# development_board.net
KiCad netlist of a schematic drawn in EAGLE
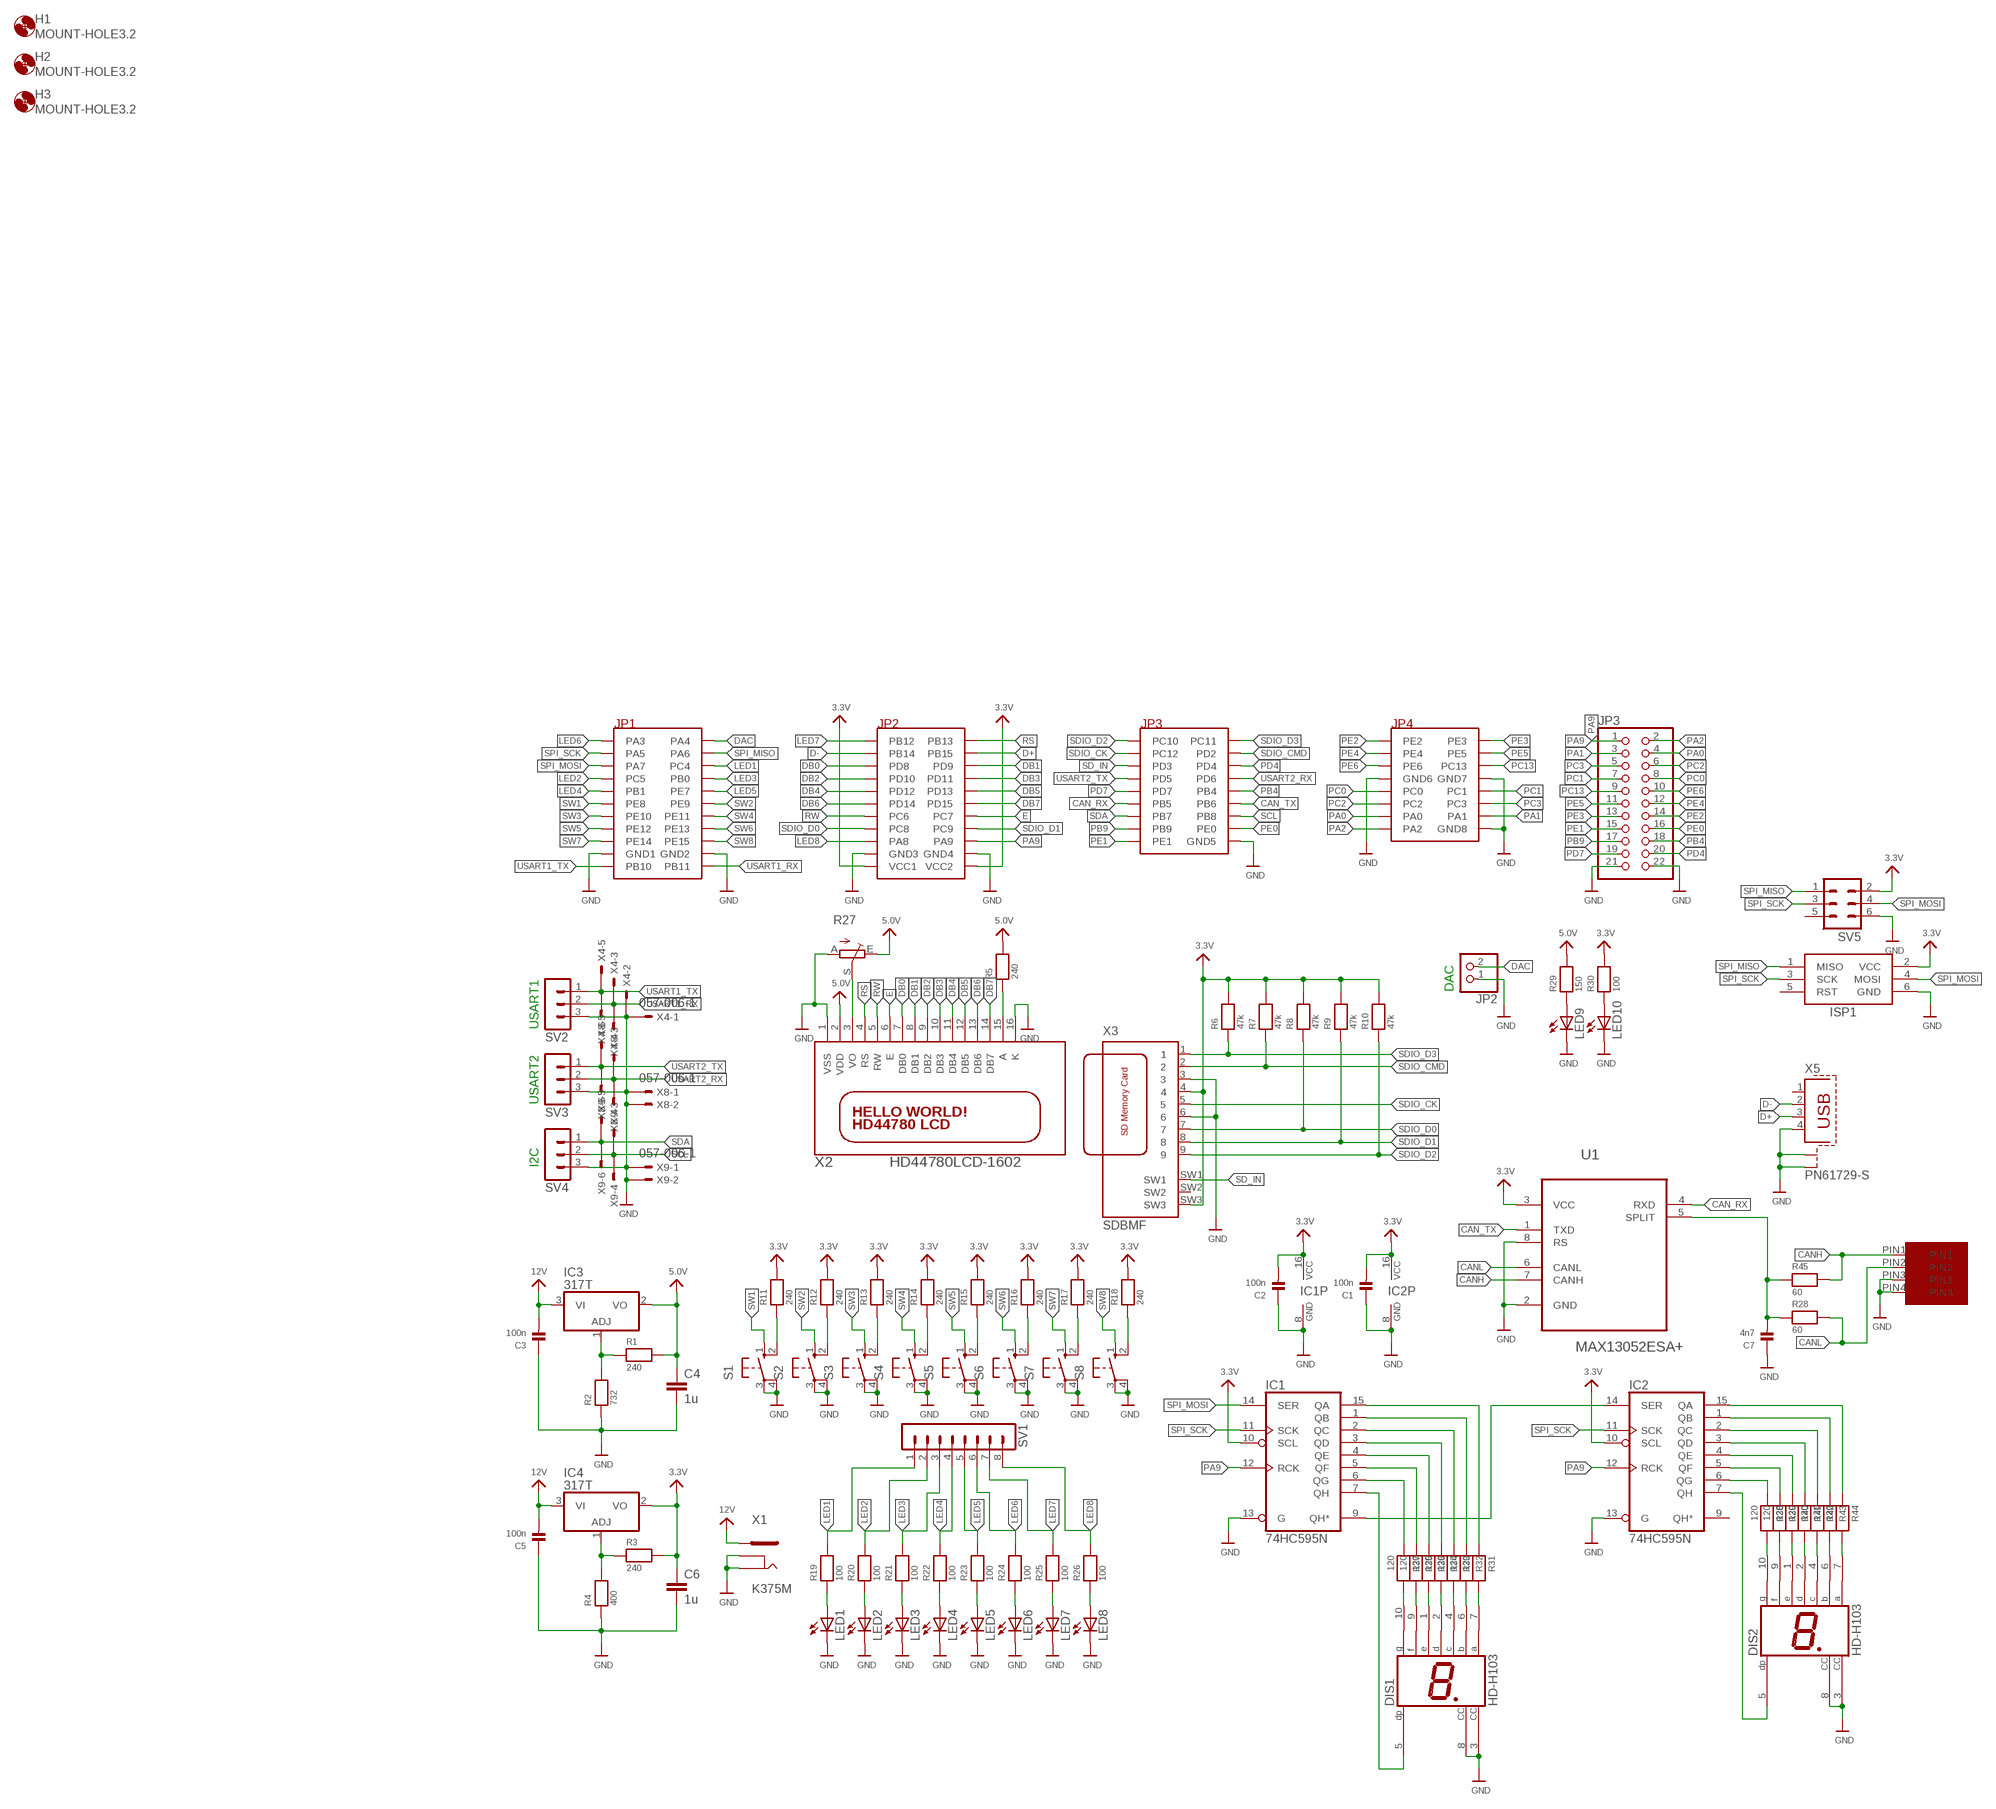
[diagram p0: schematic, sheet 1]

(export (version "E")
  (design (tool "Eeschema 10.0.6"))
  (components
    (comp (ref "C1")
      (value "100n")
      (footprint "eagle-import:_0603")
      (libsource (lib "eagle-import") (part "CAP_CERAMIC_0603"))
    )
    (comp (ref "C2")
      (value "100n")
      (footprint "eagle-import:_0603")
      (libsource (lib "eagle-import") (part "CAP_CERAMIC_0603"))
    )
    (comp (ref "C3")
      (value "100n")
      (footprint "eagle-import:_0603")
      (libsource (lib "eagle-import") (part "CAP_CERAMIC_0603"))
    )
    (comp (ref "C4")
      (value "1u")
      (footprint "eagle-import:C050-035X075")
      (libsource (lib "eagle-import") (part "C-EU050-035X075"))
    )
    (comp (ref "C5")
      (value "100n")
      (footprint "eagle-import:_0603")
      (libsource (lib "eagle-import") (part "CAP_CERAMIC_0603"))
    )
    (comp (ref "C6")
      (value "1u")
      (footprint "eagle-import:C050-035X075")
      (libsource (lib "eagle-import") (part "C-EU050-035X075"))
    )
    (comp (ref "C7")
      (value "4n7")
      (footprint "eagle-import:_0603")
      (libsource (lib "eagle-import") (part "CAP_CERAMIC_0603"))
    )
    (comp (ref "DIS1")
      (value "HD-H103")
      (footprint "eagle-import:HDSP-M")
      (libsource (lib "eagle-import") (part "HD-H103"))
    )
    (comp (ref "DIS2")
      (value "HD-H103")
      (footprint "eagle-import:HDSP-M")
      (libsource (lib "eagle-import") (part "HD-H103"))
    )
    (comp (ref "H1")
      (value "MOUNT-HOLE3.2")
      (footprint "eagle-import:3,2")
      (libsource (lib "eagle-import") (part "MOUNT-HOLE3.2"))
    )
    (comp (ref "H2")
      (value "MOUNT-HOLE3.2")
      (footprint "eagle-import:3,2")
      (libsource (lib "eagle-import") (part "MOUNT-HOLE3.2"))
    )
    (comp (ref "H3")
      (value "MOUNT-HOLE3.2")
      (footprint "eagle-import:3,2")
      (libsource (lib "eagle-import") (part "MOUNT-HOLE3.2"))
    )
    (comp (ref "IC1")
      (value "74HC595N")
      (footprint "eagle-import:DIL16")
      (libsource (lib "eagle-import") (part "74595NHC"))
    )
    (comp (ref "IC2")
      (value "74HC595N")
      (footprint "eagle-import:DIL16")
      (libsource (lib "eagle-import") (part "74595NHC"))
    )
    (comp (ref "IC3")
      (value "317T")
      (footprint "eagle-import:TO220H")
      (libsource (lib "eagle-import") (part "317T"))
    )
    (comp (ref "IC4")
      (value "317T")
      (footprint "eagle-import:TO220H")
      (libsource (lib "eagle-import") (part "317T"))
    )
    (comp (ref "ISP1")
      (value "AVRISP-BOX")
      (footprint "eagle-import:AVRISP-BOX")
      (libsource (lib "eagle-import") (part "AVRISP-BOX"))
    )
    (comp (ref "JP2")
      (value "HEADER-1X2ROUND")
      (footprint "eagle-import:1X02_ROUND")
      (libsource (lib "eagle-import") (part "HEADER-1X2ROUND"))
    )
    (comp (ref "JP3")
      (value "PINHD-2X11")
      (footprint "eagle-import:2X11")
      (libsource (lib "eagle-import") (part "PINHD-2X11"))
    )
    (comp (ref "LED1")
      (value "LED5MM")
      (footprint "eagle-import:LED5MM")
      (libsource (lib "eagle-import") (part "LED5MM"))
    )
    (comp (ref "LED2")
      (value "LED5MM")
      (footprint "eagle-import:LED5MM")
      (libsource (lib "eagle-import") (part "LED5MM"))
    )
    (comp (ref "LED3")
      (value "LED5MM")
      (footprint "eagle-import:LED5MM")
      (libsource (lib "eagle-import") (part "LED5MM"))
    )
    (comp (ref "LED4")
      (value "LED5MM")
      (footprint "eagle-import:LED5MM")
      (libsource (lib "eagle-import") (part "LED5MM"))
    )
    (comp (ref "LED5")
      (value "LED5MM")
      (footprint "eagle-import:LED5MM")
      (libsource (lib "eagle-import") (part "LED5MM"))
    )
    (comp (ref "LED6")
      (value "LED5MM")
      (footprint "eagle-import:LED5MM")
      (libsource (lib "eagle-import") (part "LED5MM"))
    )
    (comp (ref "LED7")
      (value "LED5MM")
      (footprint "eagle-import:LED5MM")
      (libsource (lib "eagle-import") (part "LED5MM"))
    )
    (comp (ref "LED8")
      (value "LED5MM")
      (footprint "eagle-import:LED5MM")
      (libsource (lib "eagle-import") (part "LED5MM"))
    )
    (comp (ref "LED9")
      (value "LED3MM")
      (footprint "eagle-import:LED3MM")
      (libsource (lib "eagle-import") (part "led_LED3MM"))
    )
    (comp (ref "LED10")
      (value "LED3MM")
      (footprint "eagle-import:LED3MM")
      (libsource (lib "eagle-import") (part "led_LED3MM"))
    )
    (comp (ref "R1")
      (value "240")
      (footprint "eagle-import:_0603")
      (libsource (lib "eagle-import") (part "RESISTOR_0603"))
    )
    (comp (ref "R2")
      (value "732")
      (footprint "eagle-import:_0603")
      (libsource (lib "eagle-import") (part "RESISTOR_0603"))
    )
    (comp (ref "R3")
      (value "240")
      (footprint "eagle-import:_0603")
      (libsource (lib "eagle-import") (part "RESISTOR_0603"))
    )
    (comp (ref "R4")
      (value "400")
      (footprint "eagle-import:_0603")
      (libsource (lib "eagle-import") (part "RESISTOR_0603"))
    )
    (comp (ref "R5")
      (value "240")
      (footprint "eagle-import:_0603")
      (libsource (lib "eagle-import") (part "RESISTOR_0603"))
    )
    (comp (ref "R6")
      (value "47k")
      (footprint "eagle-import:_0603")
      (libsource (lib "eagle-import") (part "RESISTOR_0603"))
    )
    (comp (ref "R7")
      (value "47k")
      (footprint "eagle-import:_0603")
      (libsource (lib "eagle-import") (part "RESISTOR_0603"))
    )
    (comp (ref "R8")
      (value "47k")
      (footprint "eagle-import:_0603")
      (libsource (lib "eagle-import") (part "RESISTOR_0603"))
    )
    (comp (ref "R9")
      (value "47k")
      (footprint "eagle-import:_0603")
      (libsource (lib "eagle-import") (part "RESISTOR_0603"))
    )
    (comp (ref "R10")
      (value "47k")
      (footprint "eagle-import:_0603")
      (libsource (lib "eagle-import") (part "RESISTOR_0603"))
    )
    (comp (ref "R11")
      (value "240")
      (footprint "eagle-import:_0603")
      (libsource (lib "eagle-import") (part "RESISTOR_0603"))
    )
    (comp (ref "R12")
      (value "240")
      (footprint "eagle-import:_0603")
      (libsource (lib "eagle-import") (part "RESISTOR_0603"))
    )
    (comp (ref "R13")
      (value "240")
      (footprint "eagle-import:_0603")
      (libsource (lib "eagle-import") (part "RESISTOR_0603"))
    )
    (comp (ref "R14")
      (value "240")
      (footprint "eagle-import:_0603")
      (libsource (lib "eagle-import") (part "RESISTOR_0603"))
    )
    (comp (ref "R15")
      (value "240")
      (footprint "eagle-import:_0603")
      (libsource (lib "eagle-import") (part "RESISTOR_0603"))
    )
    (comp (ref "R16")
      (value "240")
      (footprint "eagle-import:_0603")
      (libsource (lib "eagle-import") (part "RESISTOR_0603"))
    )
    (comp (ref "R17")
      (value "240")
      (footprint "eagle-import:_0603")
      (libsource (lib "eagle-import") (part "RESISTOR_0603"))
    )
    (comp (ref "R18")
      (value "240")
      (footprint "eagle-import:_0603")
      (libsource (lib "eagle-import") (part "RESISTOR_0603"))
    )
    (comp (ref "R19")
      (value "100")
      (footprint "eagle-import:_0603")
      (libsource (lib "eagle-import") (part "RESISTOR_0603"))
    )
    (comp (ref "R20")
      (value "100")
      (footprint "eagle-import:_0603")
      (libsource (lib "eagle-import") (part "RESISTOR_0603"))
    )
    (comp (ref "R21")
      (value "100")
      (footprint "eagle-import:_0603")
      (libsource (lib "eagle-import") (part "RESISTOR_0603"))
    )
    (comp (ref "R22")
      (value "100")
      (footprint "eagle-import:_0603")
      (libsource (lib "eagle-import") (part "RESISTOR_0603"))
    )
    (comp (ref "R23")
      (value "100")
      (footprint "eagle-import:_0603")
      (libsource (lib "eagle-import") (part "RESISTOR_0603"))
    )
    (comp (ref "R24")
      (value "100")
      (footprint "eagle-import:_0603")
      (libsource (lib "eagle-import") (part "RESISTOR_0603"))
    )
    (comp (ref "R25")
      (value "100")
      (footprint "eagle-import:_0603")
      (libsource (lib "eagle-import") (part "RESISTOR_0603"))
    )
    (comp (ref "R26")
      (value "100")
      (footprint "eagle-import:_0603")
      (libsource (lib "eagle-import") (part "RESISTOR_0603"))
    )
    (comp (ref "R27")
      (value "TRIM_EU-RJ9W")
      (footprint "eagle-import:RJ9W")
      (libsource (lib "eagle-import") (part "TRIM_EU-RJ9W"))
    )
    (comp (ref "R28")
      (value "60")
      (footprint "eagle-import:_0603")
      (libsource (lib "eagle-import") (part "RESISTOR_0603"))
    )
    (comp (ref "R29")
      (value "150")
      (footprint "eagle-import:_0603")
      (libsource (lib "eagle-import") (part "RESISTOR_0603"))
    )
    (comp (ref "R30")
      (value "100")
      (footprint "eagle-import:_0603")
      (libsource (lib "eagle-import") (part "RESISTOR_0603"))
    )
    (comp (ref "R31")
      (value "120")
      (footprint "eagle-import:_0603")
      (libsource (lib "eagle-import") (part "RESISTOR_0603"))
    )
    (comp (ref "R32")
      (value "120")
      (footprint "eagle-import:_0603")
      (libsource (lib "eagle-import") (part "RESISTOR_0603"))
    )
    (comp (ref "R33")
      (value "120")
      (footprint "eagle-import:_0603")
      (libsource (lib "eagle-import") (part "RESISTOR_0603"))
    )
    (comp (ref "R34")
      (value "120")
      (footprint "eagle-import:_0603")
      (libsource (lib "eagle-import") (part "RESISTOR_0603"))
    )
    (comp (ref "R35")
      (value "120")
      (footprint "eagle-import:_0603")
      (libsource (lib "eagle-import") (part "RESISTOR_0603"))
    )
    (comp (ref "R36")
      (value "120")
      (footprint "eagle-import:_0603")
      (libsource (lib "eagle-import") (part "RESISTOR_0603"))
    )
    (comp (ref "R37")
      (value "120")
      (footprint "eagle-import:_0603")
      (libsource (lib "eagle-import") (part "RESISTOR_0603"))
    )
    (comp (ref "R38")
      (value "120")
      (footprint "eagle-import:_0603")
      (libsource (lib "eagle-import") (part "RESISTOR_0603"))
    )
    (comp (ref "R39")
      (value "120")
      (footprint "eagle-import:_0603")
      (libsource (lib "eagle-import") (part "RESISTOR_0603"))
    )
    (comp (ref "R40")
      (value "120")
      (footprint "eagle-import:_0603")
      (libsource (lib "eagle-import") (part "RESISTOR_0603"))
    )
    (comp (ref "R41")
      (value "120")
      (footprint "eagle-import:_0603")
      (libsource (lib "eagle-import") (part "RESISTOR_0603"))
    )
    (comp (ref "R42")
      (value "120")
      (footprint "eagle-import:_0603")
      (libsource (lib "eagle-import") (part "RESISTOR_0603"))
    )
    (comp (ref "R43")
      (value "120")
      (footprint "eagle-import:_0603")
      (libsource (lib "eagle-import") (part "RESISTOR_0603"))
    )
    (comp (ref "R44")
      (value "120")
      (footprint "eagle-import:_0603")
      (libsource (lib "eagle-import") (part "RESISTOR_0603"))
    )
    (comp (ref "R45")
      (value "60")
      (footprint "eagle-import:_0603")
      (libsource (lib "eagle-import") (part "RESISTOR_0603"))
    )
    (comp (ref "S1")
      (value "10-XX")
      (footprint "eagle-import:B3F-10XX")
      (fields (field (name "MPN") "B3F-1000"))
      (libsource (lib "eagle-import") (part "10-XX"))
    )
    (comp (ref "S2")
      (value "10-XX")
      (footprint "eagle-import:B3F-10XX")
      (fields (field (name "MPN") "B3F-1000"))
      (libsource (lib "eagle-import") (part "10-XX"))
    )
    (comp (ref "S3")
      (value "10-XX")
      (footprint "eagle-import:B3F-10XX")
      (fields (field (name "MPN") "B3F-1000"))
      (libsource (lib "eagle-import") (part "10-XX"))
    )
    (comp (ref "S4")
      (value "10-XX")
      (footprint "eagle-import:B3F-10XX")
      (fields (field (name "MPN") "B3F-1000"))
      (libsource (lib "eagle-import") (part "10-XX"))
    )
    (comp (ref "S5")
      (value "10-XX")
      (footprint "eagle-import:B3F-10XX")
      (fields (field (name "MPN") "B3F-1000"))
      (libsource (lib "eagle-import") (part "10-XX"))
    )
    (comp (ref "S6")
      (value "10-XX")
      (footprint "eagle-import:B3F-10XX")
      (fields (field (name "MPN") "B3F-1000"))
      (libsource (lib "eagle-import") (part "10-XX"))
    )
    (comp (ref "S7")
      (value "10-XX")
      (footprint "eagle-import:B3F-10XX")
      (fields (field (name "MPN") "B3F-1000"))
      (libsource (lib "eagle-import") (part "10-XX"))
    )
    (comp (ref "S8")
      (value "10-XX")
      (footprint "eagle-import:B3F-10XX")
      (fields (field (name "MPN") "B3F-1000"))
      (libsource (lib "eagle-import") (part "10-XX"))
    )
    (comp (ref "SV1")
      (value "MA08-1")
      (footprint "eagle-import:MA08-1")
      (libsource (lib "eagle-import") (part "MA08-1"))
    )
    (comp (ref "SV2")
      (value "MA03-1")
      (footprint "eagle-import:MA03-1")
      (libsource (lib "eagle-import") (part "MA03-1"))
    )
    (comp (ref "SV3")
      (value "MA03-1")
      (footprint "eagle-import:MA03-1")
      (libsource (lib "eagle-import") (part "MA03-1"))
    )
    (comp (ref "SV4")
      (value "MA03-1")
      (footprint "eagle-import:MA03-1")
      (libsource (lib "eagle-import") (part "MA03-1"))
    )
    (comp (ref "SV5")
      (value "MA03-2")
      (footprint "eagle-import:MA03-2")
      (libsource (lib "eagle-import") (part "MA03-2"))
    )
    (comp (ref "U$1")
      (value "CPU-BOARD")
      (footprint "eagle-import:CPU-BOARD-JP1")
      (libsource (lib "eagle-import") (part "CPU-BOARD"))
    )
    (comp (ref "U$57")
      (value "MICROFIT4")
      (footprint "eagle-import:MICROFIT4SOCK")
      (libsource (lib "eagle-import") (part "MICROFIT4"))
    )
    (comp (ref "U1")
      (value "MAX13052ESA+")
      (footprint "eagle-import:SOIC127P600X175-8N")
      (libsource (lib "eagle-import") (part "MAX13052ESA+"))
    )
    (comp (ref "X1")
      (value "K375M")
      (footprint "eagle-import:K375M")
      (libsource (lib "eagle-import") (part "K375M"))
    )
    (comp (ref "X2")
      (value "HD44780LCD-1602")
      (footprint "eagle-import:LCD1602")
      (libsource (lib "eagle-import") (part "HD44780LCD-1602"))
    )
    (comp (ref "X3")
      (value "SDBMF")
      (footprint "eagle-import:SDBMF-009XXBXX2")
      (libsource (lib "eagle-import") (part "SDBMF"))
    )
    (comp (ref "X4")
      (value "057-006-1")
      (footprint "eagle-import:057-006-1")
      (fields (field (name "OC_FARNELL") "unknown") (field (name "OC_NEWARK") "unknown"))
      (libsource (lib "eagle-import") (part "057-006-1"))
    )
    (comp (ref "X5")
      (value "PN61729-S")
      (footprint "eagle-import:PN61729-S")
      (libsource (lib "eagle-import") (part "PN61729-S"))
    )
    (comp (ref "X8")
      (value "057-006-1")
      (footprint "eagle-import:057-006-1")
      (fields (field (name "OC_FARNELL") "unknown") (field (name "OC_NEWARK") "unknown"))
      (libsource (lib "eagle-import") (part "057-006-1"))
    )
    (comp (ref "X9")
      (value "057-006-1")
      (footprint "eagle-import:057-006-1")
      (fields (field (name "OC_FARNELL") "unknown") (field (name "OC_NEWARK") "unknown"))
      (libsource (lib "eagle-import") (part "057-006-1"))
    )
  )
  (nets
    (net (code "1") (name "3.3V") (class "Default")
      (node (ref "C1") (pin "2") (pinfunction "P$2_2") (pintype "passive"))
      (node (ref "C2") (pin "2") (pinfunction "P$2_2") (pintype "passive"))
      (node (ref "C6") (pin "1") (pinfunction "1_1") (pintype "passive"))
      (node (ref "IC1") (pin "10") (pinfunction "SCL_10") (pintype "input"))
      (node (ref "IC1") (pin "16") (pinfunction "VCC_16") (pintype "power_in"))
      (node (ref "IC2") (pin "10") (pinfunction "SCL_10") (pintype "input"))
      (node (ref "IC2") (pin "16") (pinfunction "VCC_16") (pintype "power_in"))
      (node (ref "IC4") (pin "2") (pinfunction "VO_2") (pintype "passive"))
      (node (ref "ISP1") (pin "2") (pinfunction "VCC_2") (pintype "power_in"))
      (node (ref "R10") (pin "2") (pinfunction "2_2") (pintype "passive"))
      (node (ref "R11") (pin "2") (pinfunction "2_2") (pintype "passive"))
      (node (ref "R12") (pin "2") (pinfunction "2_2") (pintype "passive"))
      (node (ref "R13") (pin "2") (pinfunction "2_2") (pintype "passive"))
      (node (ref "R14") (pin "2") (pinfunction "2_2") (pintype "passive"))
      (node (ref "R15") (pin "2") (pinfunction "2_2") (pintype "passive"))
      (node (ref "R16") (pin "2") (pinfunction "2_2") (pintype "passive"))
      (node (ref "R17") (pin "2") (pinfunction "2_2") (pintype "passive"))
      (node (ref "R18") (pin "2") (pinfunction "2_2") (pintype "passive"))
      (node (ref "R3") (pin "2") (pinfunction "2_2") (pintype "passive"))
      (node (ref "R30") (pin "2") (pinfunction "2_2") (pintype "passive"))
      (node (ref "R6") (pin "2") (pinfunction "2_2") (pintype "passive"))
      (node (ref "R7") (pin "2") (pinfunction "2_2") (pintype "passive"))
      (node (ref "R8") (pin "2") (pinfunction "2_2") (pintype "passive"))
      (node (ref "R9") (pin "2") (pinfunction "2_2") (pintype "passive"))
      (node (ref "SV5") (pin "2") (pinfunction "2_2") (pintype "passive"))
      (node (ref "U$1") (pin "P$43") (pinfunction "VCC1_P$43") (pintype "bidirectional"))
      (node (ref "U$1") (pin "P$44") (pinfunction "VCC2_P$44") (pintype "bidirectional"))
      (node (ref "U1") (pin "3") (pinfunction "VCC_3") (pintype "power_in"))
      (node (ref "X3") (pin "4") (pinfunction "4_4") (pintype "passive"))
      (node (ref "X3") (pin "SW3") (pinfunction "SW3_SW3") (pintype "passive"))
    )
    (net (code "2") (name "5.0V") (class "Default")
      (node (ref "C4") (pin "1") (pinfunction "1_1") (pintype "passive"))
      (node (ref "IC3") (pin "2") (pinfunction "VO_2") (pintype "passive"))
      (node (ref "R1") (pin "2") (pinfunction "2_2") (pintype "passive"))
      (node (ref "R27") (pin "E") (pinfunction "E_E") (pintype "passive"))
      (node (ref "R29") (pin "2") (pinfunction "2_2") (pintype "passive"))
      (node (ref "R5") (pin "2") (pinfunction "2_2") (pintype "passive"))
      (node (ref "X2") (pin "2") (pinfunction "VDD_2") (pintype "power_in"))
    )
    (net (code "3") (name "12V") (class "Default")
      (node (ref "C3") (pin "2") (pinfunction "P$2_2") (pintype "passive"))
      (node (ref "C5") (pin "2") (pinfunction "P$2_2") (pintype "passive"))
      (node (ref "IC3") (pin "3") (pinfunction "VI_3") (pintype "input"))
      (node (ref "IC4") (pin "3") (pinfunction "VI_3") (pintype "input"))
      (node (ref "X1") (pin "1") (pinfunction "1_1") (pintype "passive"))
    )
    (net (code "4") (name "CANH") (class "Default")
      (node (ref "R45") (pin "2") (pinfunction "2_2") (pintype "passive"))
      (node (ref "U$57") (pin "PIN1") (pinfunction "PIN1_PIN1") (pintype "bidirectional"))
      (node (ref "U1") (pin "7") (pinfunction "CANH_7") (pintype "input"))
    )
    (net (code "5") (name "CANL") (class "Default")
      (node (ref "R28") (pin "2") (pinfunction "2_2") (pintype "passive"))
      (node (ref "U$57") (pin "PIN2") (pinfunction "PIN2_PIN2") (pintype "bidirectional"))
      (node (ref "U1") (pin "6") (pinfunction "CANL_6") (pintype "input"))
    )
    (net (code "6") (name "CAN_RX") (class "Default")
      (node (ref "U$1") (pin "P$55") (pinfunction "PB5_P$55") (pintype "bidirectional"))
      (node (ref "U1") (pin "4") (pinfunction "RXD_4") (pintype "output"))
    )
    (net (code "7") (name "CAN_TX") (class "Default")
      (node (ref "U$1") (pin "P$56") (pinfunction "PB6_P$56") (pintype "bidirectional"))
      (node (ref "U1") (pin "1") (pinfunction "TXD_1") (pintype "input"))
    )
    (net (code "8") (name "D+") (class "Default")
      (node (ref "U$1") (pin "P$26") (pinfunction "PB15_P$26") (pintype "bidirectional"))
      (node (ref "X5") (pin "3") (pinfunction "3_3") (pintype "passive"))
    )
    (net (code "9") (name "D-") (class "Default")
      (node (ref "U$1") (pin "P$25") (pinfunction "PB14_P$25") (pintype "bidirectional"))
      (node (ref "X5") (pin "2") (pinfunction "2_2") (pintype "passive"))
    )
    (net (code "10") (name "DAC") (class "Default")
      (node (ref "JP2") (pin "2") (pinfunction "2_2") (pintype "passive"))
      (node (ref "U$1") (pin "P$2") (pinfunction "PA4_P$2") (pintype "bidirectional"))
    )
    (net (code "11") (name "DB0") (class "Default")
      (node (ref "U$1") (pin "P$27") (pinfunction "PD8_P$27") (pintype "bidirectional"))
      (node (ref "X2") (pin "7") (pinfunction "DB0_7") (pintype "bidirectional"))
    )
    (net (code "12") (name "DB1") (class "Default")
      (node (ref "U$1") (pin "P$28") (pinfunction "PD9_P$28") (pintype "bidirectional"))
      (node (ref "X2") (pin "8") (pinfunction "DB1_8") (pintype "bidirectional"))
    )
    (net (code "13") (name "DB2") (class "Default")
      (node (ref "U$1") (pin "P$29") (pinfunction "PD10_P$29") (pintype "bidirectional"))
      (node (ref "X2") (pin "9") (pinfunction "DB2_9") (pintype "bidirectional"))
    )
    (net (code "14") (name "DB3") (class "Default")
      (node (ref "U$1") (pin "P$30") (pinfunction "PD11_P$30") (pintype "bidirectional"))
      (node (ref "X2") (pin "10") (pinfunction "DB3_10") (pintype "bidirectional"))
    )
    (net (code "15") (name "DB4") (class "Default")
      (node (ref "U$1") (pin "P$31") (pinfunction "PD12_P$31") (pintype "bidirectional"))
      (node (ref "X2") (pin "11") (pinfunction "DB4_11") (pintype "bidirectional"))
    )
    (net (code "16") (name "DB5") (class "Default")
      (node (ref "U$1") (pin "P$32") (pinfunction "PD13_P$32") (pintype "bidirectional"))
      (node (ref "X2") (pin "12") (pinfunction "DB5_12") (pintype "bidirectional"))
    )
    (net (code "17") (name "DB6") (class "Default")
      (node (ref "U$1") (pin "P$33") (pinfunction "PD14_P$33") (pintype "bidirectional"))
      (node (ref "X2") (pin "13") (pinfunction "DB6_13") (pintype "bidirectional"))
    )
    (net (code "18") (name "DB7") (class "Default")
      (node (ref "U$1") (pin "P$34") (pinfunction "PD15_P$34") (pintype "bidirectional"))
      (node (ref "X2") (pin "14") (pinfunction "DB7_14") (pintype "bidirectional"))
    )
    (net (code "19") (name "E") (class "Default")
      (node (ref "U$1") (pin "P$36") (pinfunction "PC7_P$36") (pintype "bidirectional"))
      (node (ref "X2") (pin "6") (pinfunction "E_6") (pintype "input"))
    )
    (net (code "20") (name "GND") (class "Default")
      (node (ref "C1") (pin "1") (pinfunction "P$1_1") (pintype "passive"))
      (node (ref "C2") (pin "1") (pinfunction "P$1_1") (pintype "passive"))
      (node (ref "C3") (pin "1") (pinfunction "P$1_1") (pintype "passive"))
      (node (ref "C4") (pin "2") (pinfunction "2_2") (pintype "passive"))
      (node (ref "C5") (pin "1") (pinfunction "P$1_1") (pintype "passive"))
      (node (ref "C6") (pin "2") (pinfunction "2_2") (pintype "passive"))
      (node (ref "C7") (pin "1") (pinfunction "P$1_1") (pintype "passive"))
      (node (ref "DIS1") (pin "3") (pinfunction "CC_3") (pintype "passive"))
      (node (ref "DIS1") (pin "8") (pinfunction "CC_8") (pintype "passive"))
      (node (ref "DIS2") (pin "3") (pinfunction "CC_3") (pintype "passive"))
      (node (ref "DIS2") (pin "8") (pinfunction "CC_8") (pintype "passive"))
      (node (ref "IC1") (pin "13") (pinfunction "G_13") (pintype "input"))
      (node (ref "IC1") (pin "8") (pinfunction "GND_8") (pintype "power_in"))
      (node (ref "IC2") (pin "13") (pinfunction "G_13") (pintype "input"))
      (node (ref "IC2") (pin "8") (pinfunction "GND_8") (pintype "power_in"))
      (node (ref "ISP1") (pin "6") (pinfunction "GND_6") (pintype "power_in"))
      (node (ref "JP2") (pin "1") (pinfunction "1_1") (pintype "passive"))
      (node (ref "JP3") (pin "21") (pinfunction "21_21") (pintype "passive"))
      (node (ref "JP3") (pin "22") (pinfunction "22_22") (pintype "passive"))
      (node (ref "LED1") (pin "K") (pinfunction "C_K") (pintype "passive"))
      (node (ref "LED10") (pin "K") (pinfunction "C_K") (pintype "passive"))
      (node (ref "LED2") (pin "K") (pinfunction "C_K") (pintype "passive"))
      (node (ref "LED3") (pin "K") (pinfunction "C_K") (pintype "passive"))
      (node (ref "LED4") (pin "K") (pinfunction "C_K") (pintype "passive"))
      (node (ref "LED5") (pin "K") (pinfunction "C_K") (pintype "passive"))
      (node (ref "LED6") (pin "K") (pinfunction "C_K") (pintype "passive"))
      (node (ref "LED7") (pin "K") (pinfunction "C_K") (pintype "passive"))
      (node (ref "LED8") (pin "K") (pinfunction "C_K") (pintype "passive"))
      (node (ref "LED9") (pin "K") (pinfunction "C_K") (pintype "passive"))
      (node (ref "R2") (pin "1") (pinfunction "1_1") (pintype "passive"))
      (node (ref "R27") (pin "A") (pinfunction "A_A") (pintype "passive"))
      (node (ref "R4") (pin "1") (pinfunction "1_1") (pintype "passive"))
      (node (ref "S1") (pin "3") (pinfunction "P_3") (pintype "passive"))
      (node (ref "S1") (pin "4") (pinfunction "P1_4") (pintype "passive"))
      (node (ref "S2") (pin "3") (pinfunction "P_3") (pintype "passive"))
      (node (ref "S2") (pin "4") (pinfunction "P1_4") (pintype "passive"))
      (node (ref "S3") (pin "3") (pinfunction "P_3") (pintype "passive"))
      (node (ref "S3") (pin "4") (pinfunction "P1_4") (pintype "passive"))
      (node (ref "S4") (pin "3") (pinfunction "P_3") (pintype "passive"))
      (node (ref "S4") (pin "4") (pinfunction "P1_4") (pintype "passive"))
      (node (ref "S5") (pin "3") (pinfunction "P_3") (pintype "passive"))
      (node (ref "S5") (pin "4") (pinfunction "P1_4") (pintype "passive"))
      (node (ref "S6") (pin "3") (pinfunction "P_3") (pintype "passive"))
      (node (ref "S6") (pin "4") (pinfunction "P1_4") (pintype "passive"))
      (node (ref "S7") (pin "3") (pinfunction "P_3") (pintype "passive"))
      (node (ref "S7") (pin "4") (pinfunction "P1_4") (pintype "passive"))
      (node (ref "S8") (pin "3") (pinfunction "P_3") (pintype "passive"))
      (node (ref "S8") (pin "4") (pinfunction "P1_4") (pintype "passive"))
      (node (ref "SV2") (pin "3") (pinfunction "3_3") (pintype "passive"))
      (node (ref "SV3") (pin "3") (pinfunction "3_3") (pintype "passive"))
      (node (ref "SV4") (pin "3") (pinfunction "3_3") (pintype "passive"))
      (node (ref "SV5") (pin "6") (pinfunction "6_6") (pintype "passive"))
      (node (ref "U$1") (pin "P$21") (pinfunction "GND1_P$21") (pintype "bidirectional"))
      (node (ref "U$1") (pin "P$22") (pinfunction "GND2_P$22") (pintype "bidirectional"))
      (node (ref "U$1") (pin "P$41") (pinfunction "GND3_P$41") (pintype "bidirectional"))
      (node (ref "U$1") (pin "P$42") (pinfunction "GND4_P$42") (pintype "bidirectional"))
      (node (ref "U$1") (pin "P$62") (pinfunction "GND5_P$62") (pintype "bidirectional"))
      (node (ref "U$1") (pin "P$69") (pinfunction "GND6_P$69") (pintype "bidirectional"))
      (node (ref "U$1") (pin "P$70") (pinfunction "GND7_P$70") (pintype "bidirectional"))
      (node (ref "U$1") (pin "P$78") (pinfunction "GND8_P$78") (pintype "bidirectional"))
      (node (ref "U$57") (pin "PIN3") (pinfunction "PIN3_PIN3") (pintype "bidirectional"))
      (node (ref "U$57") (pin "PIN4") (pinfunction "PIN4_PIN4") (pintype "bidirectional"))
      (node (ref "U1") (pin "2") (pinfunction "GND_2") (pintype "passive"))
      (node (ref "U1") (pin "8") (pinfunction "RS_8") (pintype "input"))
      (node (ref "X1") (pin "2") (pinfunction "2_2") (pintype "passive"))
      (node (ref "X1") (pin "3") (pinfunction "3_3") (pintype "passive"))
      (node (ref "X2") (pin "1") (pinfunction "VSS_1") (pintype "power_in"))
      (node (ref "X2") (pin "16") (pinfunction "K_16") (pintype "input"))
      (node (ref "X3") (pin "3") (pinfunction "3_3") (pintype "passive"))
      (node (ref "X3") (pin "6") (pinfunction "6_6") (pintype "passive"))
      (node (ref "X4") (pin "1") (pinfunction "S_1") (pintype "passive"))
      (node (ref "X4") (pin "2") (pinfunction "S_2") (pintype "passive"))
      (node (ref "X5") (pin "4") (pinfunction "4_4") (pintype "passive"))
      (node (ref "X5") (pin "S1") (pinfunction "S1_S1") (pintype "passive"))
      (node (ref "X5") (pin "S2") (pinfunction "S2_S2") (pintype "passive"))
      (node (ref "X8") (pin "1") (pinfunction "S_1") (pintype "passive"))
      (node (ref "X8") (pin "2") (pinfunction "S_2") (pintype "passive"))
      (node (ref "X9") (pin "1") (pinfunction "S_1") (pintype "passive"))
      (node (ref "X9") (pin "2") (pinfunction "S_2") (pintype "passive"))
    )
    (net (code "21") (name "LED1") (class "Default")
      (node (ref "R19") (pin "2") (pinfunction "2_2") (pintype "passive"))
      (node (ref "SV1") (pin "1") (pinfunction "1_1") (pintype "passive"))
      (node (ref "U$1") (pin "P$6") (pinfunction "PC4_P$6") (pintype "bidirectional"))
    )
    (net (code "22") (name "LED2") (class "Default")
      (node (ref "R20") (pin "2") (pinfunction "2_2") (pintype "passive"))
      (node (ref "SV1") (pin "2") (pinfunction "2_2") (pintype "passive"))
      (node (ref "U$1") (pin "P$7") (pinfunction "PC5_P$7") (pintype "bidirectional"))
    )
    (net (code "23") (name "LED3") (class "Default")
      (node (ref "R21") (pin "2") (pinfunction "2_2") (pintype "passive"))
      (node (ref "SV1") (pin "3") (pinfunction "3_3") (pintype "passive"))
      (node (ref "U$1") (pin "P$8") (pinfunction "PB0_P$8") (pintype "bidirectional"))
    )
    (net (code "24") (name "LED4") (class "Default")
      (node (ref "R22") (pin "2") (pinfunction "2_2") (pintype "passive"))
      (node (ref "SV1") (pin "4") (pinfunction "4_4") (pintype "passive"))
      (node (ref "U$1") (pin "P$9") (pinfunction "PB1_P$9") (pintype "bidirectional"))
    )
    (net (code "25") (name "LED5") (class "Default")
      (node (ref "R23") (pin "2") (pinfunction "2_2") (pintype "passive"))
      (node (ref "SV1") (pin "5") (pinfunction "5_5") (pintype "passive"))
      (node (ref "U$1") (pin "P$10") (pinfunction "PE7_P$10") (pintype "bidirectional"))
    )
    (net (code "26") (name "LED6") (class "Default")
      (node (ref "R24") (pin "2") (pinfunction "2_2") (pintype "passive"))
      (node (ref "SV1") (pin "6") (pinfunction "6_6") (pintype "passive"))
      (node (ref "U$1") (pin "P$1") (pinfunction "PA3_P$1") (pintype "bidirectional"))
    )
    (net (code "27") (name "LED7") (class "Default")
      (node (ref "R25") (pin "2") (pinfunction "2_2") (pintype "passive"))
      (node (ref "SV1") (pin "7") (pinfunction "7_7") (pintype "passive"))
      (node (ref "U$1") (pin "P$23") (pinfunction "PB12_P$23") (pintype "bidirectional"))
    )
    (net (code "28") (name "LED8") (class "Default")
      (node (ref "R26") (pin "2") (pinfunction "2_2") (pintype "passive"))
      (node (ref "SV1") (pin "8") (pinfunction "8_8") (pintype "passive"))
      (node (ref "U$1") (pin "P$39") (pinfunction "PA8_P$39") (pintype "bidirectional"))
    )
    (net (code "29") (name "Net-(C7-P$2)") (class "Default")
      (node (ref "C7") (pin "2") (pinfunction "P$2_2") (pintype "passive"))
      (node (ref "R28") (pin "1") (pinfunction "1_1") (pintype "passive"))
      (node (ref "R45") (pin "1") (pinfunction "1_1") (pintype "passive"))
      (node (ref "U1") (pin "5") (pinfunction "SPLIT_5") (pintype "output"))
    )
    (net (code "30") (name "Net-(DIS1-A)") (class "Default")
      (node (ref "DIS1") (pin "7") (pinfunction "A_7") (pintype "passive"))
      (node (ref "R31") (pin "2") (pinfunction "2_2") (pintype "passive"))
    )
    (net (code "31") (name "Net-(DIS1-B)") (class "Default")
      (node (ref "DIS1") (pin "6") (pinfunction "B_6") (pintype "passive"))
      (node (ref "R32") (pin "2") (pinfunction "2_2") (pintype "passive"))
    )
    (net (code "32") (name "Net-(DIS1-C)") (class "Default")
      (node (ref "DIS1") (pin "4") (pinfunction "C_4") (pintype "passive"))
      (node (ref "R33") (pin "2") (pinfunction "2_2") (pintype "passive"))
    )
    (net (code "33") (name "Net-(DIS1-D)") (class "Default")
      (node (ref "DIS1") (pin "2") (pinfunction "D_2") (pintype "passive"))
      (node (ref "R34") (pin "2") (pinfunction "2_2") (pintype "passive"))
    )
    (net (code "34") (name "Net-(DIS1-DP)") (class "Default")
      (node (ref "DIS1") (pin "5") (pinfunction "DP_5") (pintype "passive"))
      (node (ref "IC1") (pin "7") (pinfunction "QH_7") (pintype "tri_state"))
    )
    (net (code "35") (name "Net-(DIS1-E)") (class "Default")
      (node (ref "DIS1") (pin "1") (pinfunction "E_1") (pintype "passive"))
      (node (ref "R36") (pin "2") (pinfunction "2_2") (pintype "passive"))
    )
    (net (code "36") (name "Net-(DIS1-F)") (class "Default")
      (node (ref "DIS1") (pin "9") (pinfunction "F_9") (pintype "passive"))
      (node (ref "R35") (pin "2") (pinfunction "2_2") (pintype "passive"))
    )
    (net (code "37") (name "Net-(DIS1-G)") (class "Default")
      (node (ref "DIS1") (pin "10") (pinfunction "G_10") (pintype "passive"))
      (node (ref "R37") (pin "2") (pinfunction "2_2") (pintype "passive"))
    )
    (net (code "38") (name "Net-(DIS2-A)") (class "Default")
      (node (ref "DIS2") (pin "7") (pinfunction "A_7") (pintype "passive"))
      (node (ref "R44") (pin "2") (pinfunction "2_2") (pintype "passive"))
    )
    (net (code "39") (name "Net-(DIS2-B)") (class "Default")
      (node (ref "DIS2") (pin "6") (pinfunction "B_6") (pintype "passive"))
      (node (ref "R43") (pin "2") (pinfunction "2_2") (pintype "passive"))
    )
    (net (code "40") (name "Net-(DIS2-C)") (class "Default")
      (node (ref "DIS2") (pin "4") (pinfunction "C_4") (pintype "passive"))
      (node (ref "R42") (pin "2") (pinfunction "2_2") (pintype "passive"))
    )
    (net (code "41") (name "Net-(DIS2-D)") (class "Default")
      (node (ref "DIS2") (pin "2") (pinfunction "D_2") (pintype "passive"))
      (node (ref "R41") (pin "2") (pinfunction "2_2") (pintype "passive"))
    )
    (net (code "42") (name "Net-(DIS2-DP)") (class "Default")
      (node (ref "DIS2") (pin "5") (pinfunction "DP_5") (pintype "passive"))
      (node (ref "IC2") (pin "7") (pinfunction "QH_7") (pintype "tri_state"))
    )
    (net (code "43") (name "Net-(DIS2-E)") (class "Default")
      (node (ref "DIS2") (pin "1") (pinfunction "E_1") (pintype "passive"))
      (node (ref "R40") (pin "2") (pinfunction "2_2") (pintype "passive"))
    )
    (net (code "44") (name "Net-(DIS2-F)") (class "Default")
      (node (ref "DIS2") (pin "9") (pinfunction "F_9") (pintype "passive"))
      (node (ref "R39") (pin "2") (pinfunction "2_2") (pintype "passive"))
    )
    (net (code "45") (name "Net-(DIS2-G)") (class "Default")
      (node (ref "DIS2") (pin "10") (pinfunction "G_10") (pintype "passive"))
      (node (ref "R38") (pin "2") (pinfunction "2_2") (pintype "passive"))
    )
    (net (code "46") (name "Net-(IC1A-QA)") (class "Default")
      (node (ref "IC1") (pin "15") (pinfunction "QA_15") (pintype "tri_state"))
      (node (ref "R31") (pin "1") (pinfunction "1_1") (pintype "passive"))
    )
    (net (code "47") (name "Net-(IC1A-QB)") (class "Default")
      (node (ref "IC1") (pin "1") (pinfunction "QB_1") (pintype "tri_state"))
      (node (ref "R32") (pin "1") (pinfunction "1_1") (pintype "passive"))
    )
    (net (code "48") (name "Net-(IC1A-QC)") (class "Default")
      (node (ref "IC1") (pin "2") (pinfunction "QC_2") (pintype "tri_state"))
      (node (ref "R33") (pin "1") (pinfunction "1_1") (pintype "passive"))
    )
    (net (code "49") (name "Net-(IC1A-QD)") (class "Default")
      (node (ref "IC1") (pin "3") (pinfunction "QD_3") (pintype "tri_state"))
      (node (ref "R34") (pin "1") (pinfunction "1_1") (pintype "passive"))
    )
    (net (code "50") (name "Net-(IC1A-QE)") (class "Default")
      (node (ref "IC1") (pin "4") (pinfunction "QE_4") (pintype "tri_state"))
      (node (ref "R36") (pin "1") (pinfunction "1_1") (pintype "passive"))
    )
    (net (code "51") (name "Net-(IC1A-QF)") (class "Default")
      (node (ref "IC1") (pin "5") (pinfunction "QF_5") (pintype "tri_state"))
      (node (ref "R35") (pin "1") (pinfunction "1_1") (pintype "passive"))
    )
    (net (code "52") (name "Net-(IC1A-QG)") (class "Default")
      (node (ref "IC1") (pin "6") (pinfunction "QG_6") (pintype "tri_state"))
      (node (ref "R37") (pin "1") (pinfunction "1_1") (pintype "passive"))
    )
    (net (code "53") (name "Net-(IC1A-QH*)") (class "Default")
      (node (ref "IC1") (pin "9") (pinfunction "QH*_9") (pintype "tri_state"))
      (node (ref "IC2") (pin "14") (pinfunction "SER_14") (pintype "input"))
    )
    (net (code "54") (name "Net-(IC2A-QA)") (class "Default")
      (node (ref "IC2") (pin "15") (pinfunction "QA_15") (pintype "tri_state"))
      (node (ref "R44") (pin "1") (pinfunction "1_1") (pintype "passive"))
    )
    (net (code "55") (name "Net-(IC2A-QB)") (class "Default")
      (node (ref "IC2") (pin "1") (pinfunction "QB_1") (pintype "tri_state"))
      (node (ref "R43") (pin "1") (pinfunction "1_1") (pintype "passive"))
    )
    (net (code "56") (name "Net-(IC2A-QC)") (class "Default")
      (node (ref "IC2") (pin "2") (pinfunction "QC_2") (pintype "tri_state"))
      (node (ref "R42") (pin "1") (pinfunction "1_1") (pintype "passive"))
    )
    (net (code "57") (name "Net-(IC2A-QD)") (class "Default")
      (node (ref "IC2") (pin "3") (pinfunction "QD_3") (pintype "tri_state"))
      (node (ref "R41") (pin "1") (pinfunction "1_1") (pintype "passive"))
    )
    (net (code "58") (name "Net-(IC2A-QE)") (class "Default")
      (node (ref "IC2") (pin "4") (pinfunction "QE_4") (pintype "tri_state"))
      (node (ref "R40") (pin "1") (pinfunction "1_1") (pintype "passive"))
    )
    (net (code "59") (name "Net-(IC2A-QF)") (class "Default")
      (node (ref "IC2") (pin "5") (pinfunction "QF_5") (pintype "tri_state"))
      (node (ref "R39") (pin "1") (pinfunction "1_1") (pintype "passive"))
    )
    (net (code "60") (name "Net-(IC2A-QG)") (class "Default")
      (node (ref "IC2") (pin "6") (pinfunction "QG_6") (pintype "tri_state"))
      (node (ref "R38") (pin "1") (pinfunction "1_1") (pintype "passive"))
    )
    (net (code "61") (name "Net-(IC3-ADJ)") (class "Default")
      (node (ref "IC3") (pin "1") (pinfunction "ADJ_1") (pintype "input"))
      (node (ref "R1") (pin "1") (pinfunction "1_1") (pintype "passive"))
      (node (ref "R2") (pin "2") (pinfunction "2_2") (pintype "passive"))
    )
    (net (code "62") (name "Net-(IC4-ADJ)") (class "Default")
      (node (ref "IC4") (pin "1") (pinfunction "ADJ_1") (pintype "input"))
      (node (ref "R3") (pin "1") (pinfunction "1_1") (pintype "passive"))
      (node (ref "R4") (pin "2") (pinfunction "2_2") (pintype "passive"))
    )
    (net (code "63") (name "Net-(LED1-PadA)") (class "Default")
      (node (ref "LED1") (pin "A") (pinfunction "A_A") (pintype "passive"))
      (node (ref "R19") (pin "1") (pinfunction "1_1") (pintype "passive"))
    )
    (net (code "64") (name "Net-(LED2-PadA)") (class "Default")
      (node (ref "LED2") (pin "A") (pinfunction "A_A") (pintype "passive"))
      (node (ref "R20") (pin "1") (pinfunction "1_1") (pintype "passive"))
    )
    (net (code "65") (name "Net-(LED3-PadA)") (class "Default")
      (node (ref "LED3") (pin "A") (pinfunction "A_A") (pintype "passive"))
      (node (ref "R21") (pin "1") (pinfunction "1_1") (pintype "passive"))
    )
    (net (code "66") (name "Net-(LED4-PadA)") (class "Default")
      (node (ref "LED4") (pin "A") (pinfunction "A_A") (pintype "passive"))
      (node (ref "R22") (pin "1") (pinfunction "1_1") (pintype "passive"))
    )
    (net (code "67") (name "Net-(LED5-PadA)") (class "Default")
      (node (ref "LED5") (pin "A") (pinfunction "A_A") (pintype "passive"))
      (node (ref "R23") (pin "1") (pinfunction "1_1") (pintype "passive"))
    )
    (net (code "68") (name "Net-(LED6-PadA)") (class "Default")
      (node (ref "LED6") (pin "A") (pinfunction "A_A") (pintype "passive"))
      (node (ref "R24") (pin "1") (pinfunction "1_1") (pintype "passive"))
    )
    (net (code "69") (name "Net-(LED7-PadA)") (class "Default")
      (node (ref "LED7") (pin "A") (pinfunction "A_A") (pintype "passive"))
      (node (ref "R25") (pin "1") (pinfunction "1_1") (pintype "passive"))
    )
    (net (code "70") (name "Net-(LED8-PadA)") (class "Default")
      (node (ref "LED8") (pin "A") (pinfunction "A_A") (pintype "passive"))
      (node (ref "R26") (pin "1") (pinfunction "1_1") (pintype "passive"))
    )
    (net (code "71") (name "Net-(LED9-PadA)") (class "Default")
      (node (ref "LED9") (pin "A") (pinfunction "A_A") (pintype "passive"))
      (node (ref "R29") (pin "1") (pinfunction "1_1") (pintype "passive"))
    )
    (net (code "72") (name "Net-(LED10-PadA)") (class "Default")
      (node (ref "LED10") (pin "A") (pinfunction "A_A") (pintype "passive"))
      (node (ref "R30") (pin "1") (pinfunction "1_1") (pintype "passive"))
    )
    (net (code "73") (name "Net-(S1-S1)") (class "Default")
      (node (ref "R11") (pin "1") (pinfunction "1_1") (pintype "passive"))
      (node (ref "S1") (pin "2") (pinfunction "S1_2") (pintype "passive"))
    )
    (net (code "74") (name "Net-(S2-S1)") (class "Default")
      (node (ref "R12") (pin "1") (pinfunction "1_1") (pintype "passive"))
      (node (ref "S2") (pin "2") (pinfunction "S1_2") (pintype "passive"))
    )
    (net (code "75") (name "Net-(S3-S1)") (class "Default")
      (node (ref "R13") (pin "1") (pinfunction "1_1") (pintype "passive"))
      (node (ref "S3") (pin "2") (pinfunction "S1_2") (pintype "passive"))
    )
    (net (code "76") (name "Net-(S4-S1)") (class "Default")
      (node (ref "R14") (pin "1") (pinfunction "1_1") (pintype "passive"))
      (node (ref "S4") (pin "2") (pinfunction "S1_2") (pintype "passive"))
    )
    (net (code "77") (name "Net-(S5-S1)") (class "Default")
      (node (ref "R15") (pin "1") (pinfunction "1_1") (pintype "passive"))
      (node (ref "S5") (pin "2") (pinfunction "S1_2") (pintype "passive"))
    )
    (net (code "78") (name "Net-(S6-S1)") (class "Default")
      (node (ref "R16") (pin "1") (pinfunction "1_1") (pintype "passive"))
      (node (ref "S6") (pin "2") (pinfunction "S1_2") (pintype "passive"))
    )
    (net (code "79") (name "Net-(S7-S1)") (class "Default")
      (node (ref "R17") (pin "1") (pinfunction "1_1") (pintype "passive"))
      (node (ref "S7") (pin "2") (pinfunction "S1_2") (pintype "passive"))
    )
    (net (code "80") (name "Net-(S8-S1)") (class "Default")
      (node (ref "R18") (pin "1") (pinfunction "1_1") (pintype "passive"))
      (node (ref "S8") (pin "2") (pinfunction "S1_2") (pintype "passive"))
    )
    (net (code "81") (name "Net-(X2-A)") (class "Default")
      (node (ref "R5") (pin "1") (pinfunction "1_1") (pintype "passive"))
      (node (ref "X2") (pin "15") (pinfunction "A_15") (pintype "input"))
    )
    (net (code "82") (name "Net-(X2-VO)") (class "Default")
      (node (ref "R27") (pin "S") (pinfunction "S_S") (pintype "passive"))
      (node (ref "X2") (pin "3") (pinfunction "VO_3") (pintype "input"))
    )
    (net (code "83") (name "PA0") (class "Default")
      (node (ref "JP3") (pin "4") (pinfunction "4_4") (pintype "passive"))
      (node (ref "U$1") (pin "P$75") (pinfunction "PA0_P$75") (pintype "bidirectional"))
    )
    (net (code "84") (name "PA1") (class "Default")
      (node (ref "JP3") (pin "3") (pinfunction "3_3") (pintype "passive"))
      (node (ref "U$1") (pin "P$76") (pinfunction "PA1_P$76") (pintype "bidirectional"))
    )
    (net (code "85") (name "PA2") (class "Default")
      (node (ref "JP3") (pin "2") (pinfunction "2_2") (pintype "passive"))
      (node (ref "U$1") (pin "P$77") (pinfunction "PA2_P$77") (pintype "bidirectional"))
    )
    (net (code "86") (name "PA9") (class "Default")
      (node (ref "IC1") (pin "12") (pinfunction "RCK_12") (pintype "input"))
      (node (ref "IC2") (pin "12") (pinfunction "RCK_12") (pintype "input"))
      (node (ref "JP3") (pin "1") (pinfunction "1_1") (pintype "passive"))
      (node (ref "U$1") (pin "P$40") (pinfunction "PA9_P$40") (pintype "bidirectional"))
    )
    (net (code "87") (name "PB4") (class "Default")
      (node (ref "JP3") (pin "18") (pinfunction "18_18") (pintype "passive"))
      (node (ref "U$1") (pin "P$54") (pinfunction "PB4_P$54") (pintype "bidirectional"))
    )
    (net (code "88") (name "PB9") (class "Default")
      (node (ref "JP3") (pin "17") (pinfunction "17_17") (pintype "passive"))
      (node (ref "U$1") (pin "P$59") (pinfunction "PB9_P$59") (pintype "bidirectional"))
    )
    (net (code "89") (name "PC0") (class "Default")
      (node (ref "JP3") (pin "8") (pinfunction "8_8") (pintype "passive"))
      (node (ref "U$1") (pin "P$71") (pinfunction "PC0_P$71") (pintype "bidirectional"))
    )
    (net (code "90") (name "PC1") (class "Default")
      (node (ref "JP3") (pin "7") (pinfunction "7_7") (pintype "passive"))
      (node (ref "U$1") (pin "P$72") (pinfunction "PC1_P$72") (pintype "bidirectional"))
    )
    (net (code "91") (name "PC2") (class "Default")
      (node (ref "JP3") (pin "6") (pinfunction "6_6") (pintype "passive"))
      (node (ref "U$1") (pin "P$73") (pinfunction "PC2_P$73") (pintype "bidirectional"))
    )
    (net (code "92") (name "PC3") (class "Default")
      (node (ref "JP3") (pin "5") (pinfunction "5_5") (pintype "passive"))
      (node (ref "U$1") (pin "P$74") (pinfunction "PC3_P$74") (pintype "bidirectional"))
    )
    (net (code "93") (name "PC13") (class "Default")
      (node (ref "JP3") (pin "9") (pinfunction "9_9") (pintype "passive"))
      (node (ref "U$1") (pin "P$68") (pinfunction "PC13_P$68") (pintype "bidirectional"))
    )
    (net (code "94") (name "PD4") (class "Default")
      (node (ref "JP3") (pin "20") (pinfunction "20_20") (pintype "passive"))
      (node (ref "U$1") (pin "P$50") (pinfunction "PD4_P$50") (pintype "bidirectional"))
    )
    (net (code "95") (name "PD7") (class "Default")
      (node (ref "JP3") (pin "19") (pinfunction "19_19") (pintype "passive"))
      (node (ref "U$1") (pin "P$53") (pinfunction "PD7_P$53") (pintype "bidirectional"))
    )
    (net (code "96") (name "PE0") (class "Default")
      (node (ref "JP3") (pin "16") (pinfunction "16_16") (pintype "passive"))
      (node (ref "U$1") (pin "P$60") (pinfunction "PE0_P$60") (pintype "bidirectional"))
    )
    (net (code "97") (name "PE1") (class "Default")
      (node (ref "JP3") (pin "15") (pinfunction "15_15") (pintype "passive"))
      (node (ref "U$1") (pin "P$61") (pinfunction "PE1_P$61") (pintype "bidirectional"))
    )
    (net (code "98") (name "PE2") (class "Default")
      (node (ref "JP3") (pin "14") (pinfunction "14_14") (pintype "passive"))
      (node (ref "U$1") (pin "P$63") (pinfunction "PE2_P$63") (pintype "bidirectional"))
    )
    (net (code "99") (name "PE3") (class "Default")
      (node (ref "JP3") (pin "13") (pinfunction "13_13") (pintype "passive"))
      (node (ref "U$1") (pin "P$64") (pinfunction "PE3_P$64") (pintype "bidirectional"))
    )
    (net (code "100") (name "PE4") (class "Default")
      (node (ref "JP3") (pin "12") (pinfunction "12_12") (pintype "passive"))
      (node (ref "U$1") (pin "P$65") (pinfunction "PE4_P$65") (pintype "bidirectional"))
    )
    (net (code "101") (name "PE5") (class "Default")
      (node (ref "JP3") (pin "11") (pinfunction "11_11") (pintype "passive"))
      (node (ref "U$1") (pin "P$66") (pinfunction "PE5_P$66") (pintype "bidirectional"))
    )
    (net (code "102") (name "PE6") (class "Default")
      (node (ref "JP3") (pin "10") (pinfunction "10_10") (pintype "passive"))
      (node (ref "U$1") (pin "P$67") (pinfunction "PE6_P$67") (pintype "bidirectional"))
    )
    (net (code "103") (name "RS") (class "Default")
      (node (ref "U$1") (pin "P$24") (pinfunction "PB13_P$24") (pintype "bidirectional"))
      (node (ref "X2") (pin "4") (pinfunction "RS_4") (pintype "input"))
    )
    (net (code "104") (name "RW") (class "Default")
      (node (ref "U$1") (pin "P$35") (pinfunction "PC6_P$35") (pintype "bidirectional"))
      (node (ref "X2") (pin "5") (pinfunction "RW_5") (pintype "input"))
    )
    (net (code "105") (name "SCL") (class "Default")
      (node (ref "SV4") (pin "2") (pinfunction "2_2") (pintype "passive"))
      (node (ref "U$1") (pin "P$58") (pinfunction "PB8_P$58") (pintype "bidirectional"))
      (node (ref "X9") (pin "3") (pinfunction "S_3") (pintype "passive"))
      (node (ref "X9") (pin "4") (pinfunction "S_4") (pintype "passive"))
    )
    (net (code "106") (name "SDA") (class "Default")
      (node (ref "SV4") (pin "1") (pinfunction "1_1") (pintype "passive"))
      (node (ref "U$1") (pin "P$57") (pinfunction "PB7_P$57") (pintype "bidirectional"))
      (node (ref "X9") (pin "5") (pinfunction "S_5") (pintype "passive"))
      (node (ref "X9") (pin "6") (pinfunction "S_6") (pintype "passive"))
    )
    (net (code "107") (name "SDIO_CK") (class "Default")
      (node (ref "U$1") (pin "P$47") (pinfunction "PC12_P$47") (pintype "bidirectional"))
      (node (ref "X3") (pin "5") (pinfunction "5_5") (pintype "passive"))
    )
    (net (code "108") (name "SDIO_CMD") (class "Default")
      (node (ref "R7") (pin "1") (pinfunction "1_1") (pintype "passive"))
      (node (ref "U$1") (pin "P$48") (pinfunction "PD2_P$48") (pintype "bidirectional"))
      (node (ref "X3") (pin "2") (pinfunction "2_2") (pintype "passive"))
    )
    (net (code "109") (name "SDIO_D0") (class "Default")
      (node (ref "R8") (pin "1") (pinfunction "1_1") (pintype "passive"))
      (node (ref "U$1") (pin "P$37") (pinfunction "PC8_P$37") (pintype "bidirectional"))
      (node (ref "X3") (pin "7") (pinfunction "7_7") (pintype "passive"))
    )
    (net (code "110") (name "SDIO_D1") (class "Default")
      (node (ref "R9") (pin "1") (pinfunction "1_1") (pintype "passive"))
      (node (ref "U$1") (pin "P$38") (pinfunction "PC9_P$38") (pintype "bidirectional"))
      (node (ref "X3") (pin "8") (pinfunction "8_8") (pintype "passive"))
    )
    (net (code "111") (name "SDIO_D2") (class "Default")
      (node (ref "R10") (pin "1") (pinfunction "1_1") (pintype "passive"))
      (node (ref "U$1") (pin "P$45") (pinfunction "PC10_P$45") (pintype "bidirectional"))
      (node (ref "X3") (pin "9") (pinfunction "9_9") (pintype "passive"))
    )
    (net (code "112") (name "SDIO_D3") (class "Default")
      (node (ref "R6") (pin "1") (pinfunction "1_1") (pintype "passive"))
      (node (ref "U$1") (pin "P$46") (pinfunction "PC11_P$46") (pintype "bidirectional"))
      (node (ref "X3") (pin "1") (pinfunction "1_1") (pintype "passive"))
    )
    (net (code "113") (name "SD_IN") (class "Default")
      (node (ref "U$1") (pin "P$49") (pinfunction "PD3_P$49") (pintype "bidirectional"))
      (node (ref "X3") (pin "SW1") (pinfunction "SW1_SW1") (pintype "passive"))
    )
    (net (code "114") (name "SPI_MISO") (class "Default")
      (node (ref "ISP1") (pin "1") (pinfunction "MISO_1") (pintype "input"))
      (node (ref "SV5") (pin "1") (pinfunction "1_1") (pintype "passive"))
      (node (ref "U$1") (pin "P$4") (pinfunction "PA6_P$4") (pintype "bidirectional"))
    )
    (net (code "115") (name "SPI_MOSI") (class "Default")
      (node (ref "IC1") (pin "14") (pinfunction "SER_14") (pintype "input"))
      (node (ref "ISP1") (pin "4") (pinfunction "MOSI_4") (pintype "output"))
      (node (ref "SV5") (pin "4") (pinfunction "4_4") (pintype "passive"))
      (node (ref "U$1") (pin "P$5") (pinfunction "PA7_P$5") (pintype "bidirectional"))
    )
    (net (code "116") (name "SPI_SCK") (class "Default")
      (node (ref "IC1") (pin "11") (pinfunction "SCK_11") (pintype "input"))
      (node (ref "IC2") (pin "11") (pinfunction "SCK_11") (pintype "input"))
      (node (ref "ISP1") (pin "3") (pinfunction "SCK_3") (pintype "output"))
      (node (ref "SV5") (pin "3") (pinfunction "3_3") (pintype "passive"))
      (node (ref "U$1") (pin "P$3") (pinfunction "PA5_P$3") (pintype "bidirectional"))
    )
    (net (code "117") (name "SW1") (class "Default")
      (node (ref "S1") (pin "1") (pinfunction "S_1") (pintype "passive"))
      (node (ref "U$1") (pin "P$11") (pinfunction "PE8_P$11") (pintype "bidirectional"))
    )
    (net (code "118") (name "SW2") (class "Default")
      (node (ref "S2") (pin "1") (pinfunction "S_1") (pintype "passive"))
      (node (ref "U$1") (pin "P$12") (pinfunction "PE9_P$12") (pintype "bidirectional"))
    )
    (net (code "119") (name "SW3") (class "Default")
      (node (ref "S3") (pin "1") (pinfunction "S_1") (pintype "passive"))
      (node (ref "U$1") (pin "P$13") (pinfunction "PE10_P$13") (pintype "bidirectional"))
    )
    (net (code "120") (name "SW4") (class "Default")
      (node (ref "S4") (pin "1") (pinfunction "S_1") (pintype "passive"))
      (node (ref "U$1") (pin "P$14") (pinfunction "PE11_P$14") (pintype "bidirectional"))
    )
    (net (code "121") (name "SW5") (class "Default")
      (node (ref "S5") (pin "1") (pinfunction "S_1") (pintype "passive"))
      (node (ref "U$1") (pin "P$15") (pinfunction "PE12_P$15") (pintype "bidirectional"))
    )
    (net (code "122") (name "SW6") (class "Default")
      (node (ref "S6") (pin "1") (pinfunction "S_1") (pintype "passive"))
      (node (ref "U$1") (pin "P$16") (pinfunction "PE13_P$16") (pintype "bidirectional"))
    )
    (net (code "123") (name "SW7") (class "Default")
      (node (ref "S7") (pin "1") (pinfunction "S_1") (pintype "passive"))
      (node (ref "U$1") (pin "P$17") (pinfunction "PE14_P$17") (pintype "bidirectional"))
    )
    (net (code "124") (name "SW8") (class "Default")
      (node (ref "S8") (pin "1") (pinfunction "S_1") (pintype "passive"))
      (node (ref "U$1") (pin "P$18") (pinfunction "PE15_P$18") (pintype "bidirectional"))
    )
    (net (code "125") (name "USART1_RX") (class "Default")
      (node (ref "SV2") (pin "2") (pinfunction "2_2") (pintype "passive"))
      (node (ref "U$1") (pin "P$20") (pinfunction "PB11_P$20") (pintype "bidirectional"))
      (node (ref "X4") (pin "3") (pinfunction "S_3") (pintype "passive"))
      (node (ref "X4") (pin "4") (pinfunction "S_4") (pintype "passive"))
    )
    (net (code "126") (name "USART1_TX") (class "Default")
      (node (ref "SV2") (pin "1") (pinfunction "1_1") (pintype "passive"))
      (node (ref "U$1") (pin "P$19") (pinfunction "PB10_P$19") (pintype "bidirectional"))
      (node (ref "X4") (pin "5") (pinfunction "S_5") (pintype "passive"))
      (node (ref "X4") (pin "6") (pinfunction "S_6") (pintype "passive"))
    )
    (net (code "127") (name "USART2_RX") (class "Default")
      (node (ref "SV3") (pin "2") (pinfunction "2_2") (pintype "passive"))
      (node (ref "U$1") (pin "P$52") (pinfunction "PD6_P$52") (pintype "bidirectional"))
      (node (ref "X8") (pin "3") (pinfunction "S_3") (pintype "passive"))
      (node (ref "X8") (pin "4") (pinfunction "S_4") (pintype "passive"))
    )
    (net (code "128") (name "USART2_TX") (class "Default")
      (node (ref "SV3") (pin "1") (pinfunction "1_1") (pintype "passive"))
      (node (ref "U$1") (pin "P$51") (pinfunction "PD5_P$51") (pintype "bidirectional"))
      (node (ref "X8") (pin "5") (pinfunction "S_5") (pintype "passive"))
      (node (ref "X8") (pin "6") (pinfunction "S_6") (pintype "passive"))
    )
    (net (code "129") (name "unconnected-(IC2A-QH*-Pad9)") (class "Default")
      (node (ref "IC2") (pin "9") (pinfunction "QH*_9") (pintype "tri_state"))
    )
    (net (code "130") (name "unconnected-(ISP1-RST-Pad5)") (class "Default")
      (node (ref "ISP1") (pin "5") (pinfunction "RST_5") (pintype "output"))
    )
    (net (code "131") (name "unconnected-(SV5-Pad5)") (class "Default")
      (node (ref "SV5") (pin "5") (pinfunction "5_5") (pintype "passive"))
    )
    (net (code "132") (name "unconnected-(X3-PadSW2)") (class "Default")
      (node (ref "X3") (pin "SW2") (pinfunction "SW2_SW2") (pintype "passive"))
    )
    (net (code "133") (name "unconnected-(X5-Pad1)") (class "Default")
      (node (ref "X5") (pin "1") (pinfunction "1_1") (pintype "passive"))
    )
  )
)
